# 1_ADC.net
KiCad netlist of a schematic drawn in Altium Designer
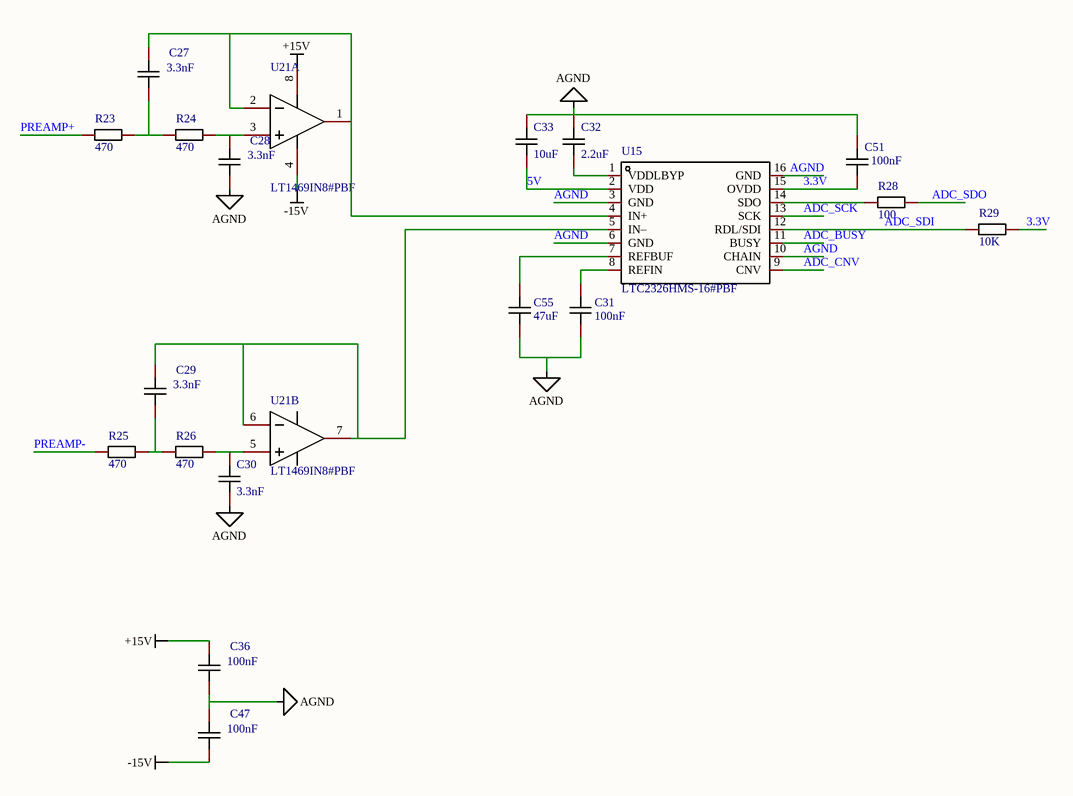
[diagram p0: 1_ADC.schdoc]

(export (version "E")
  (design (tool "Eeschema 10.0.6"))
  (components
    (comp (ref "C27")
      (value "3.3nF")
      (description "容值:100nF;精度:±10%;额定电压:25V;温度系数:X7R;")
      (fields
        (field (name "MANUFACTURER") "SAMSUNG(三星)")
        (field (name "MANUFACTURER PART") "CL10B104KA8NNNC")
      )
      (libsource (lib "altium-import") (part "root_1_CL10B104KA8NNNC_"))
    )
    (comp (ref "C28")
      (value "3.3nF")
      (description "容值:100nF;精度:±10%;额定电压:25V;温度系数:X7R;")
      (fields
        (field (name "MANUFACTURER") "SAMSUNG(三星)")
        (field (name "MANUFACTURER PART") "CL10B104KA8NNNC")
      )
      (libsource (lib "altium-import") (part "root_1_CL10B104KA8NNNC_"))
    )
    (comp (ref "C29")
      (value "3.3nF")
      (description "容值:100nF;精度:±10%;额定电压:25V;温度系数:X7R;")
      (fields
        (field (name "MANUFACTURER") "SAMSUNG(三星)")
        (field (name "MANUFACTURER PART") "CL10B104KA8NNNC")
      )
      (libsource (lib "altium-import") (part "root_1_CL10B104KA8NNNC_"))
    )
    (comp (ref "C30")
      (value "3.3nF")
      (description "容值:100nF;精度:±10%;额定电压:25V;温度系数:X7R;")
      (fields
        (field (name "MANUFACTURER") "SAMSUNG(三星)")
        (field (name "MANUFACTURER PART") "CL10B104KA8NNNC")
      )
      (libsource (lib "altium-import") (part "root_1_CL10B104KA8NNNC_"))
    )
    (comp (ref "C31")
      (value "100nF")
      (description "容值:100nF;精度:±10%;额定电压:25V;温度系数:X7R;")
      (fields
        (field (name "MANUFACTURER") "SAMSUNG(三星)")
        (field (name "MANUFACTURER PART") "CL10B104KA8NNNC")
      )
      (libsource (lib "altium-import") (part "root_1_CL10B104KA8NNNC_"))
    )
    (comp (ref "C32")
      (value "2.2uF")
      (description "容值:100nF;精度:±10%;额定电压:25V;温度系数:X7R;")
      (fields
        (field (name "MANUFACTURER") "SAMSUNG(三星)")
        (field (name "MANUFACTURER PART") "CL10B104KA8NNNC")
      )
      (libsource (lib "altium-import") (part "root_1_CL10B104KA8NNNC_"))
    )
    (comp (ref "C33")
      (value "10uF")
      (description "容值:100nF;精度:±10%;额定电压:25V;温度系数:X7R;")
      (fields
        (field (name "MANUFACTURER") "SAMSUNG(三星)")
        (field (name "MANUFACTURER PART") "CL10B104KA8NNNC")
      )
      (libsource (lib "altium-import") (part "root_1_CL10B104KA8NNNC_"))
    )
    (comp (ref "C36")
      (value "100nF")
      (description "容值:100nF;精度:±10%;额定电压:25V;温度系数:X7R;")
      (fields
        (field (name "MANUFACTURER") "SAMSUNG(三星)")
        (field (name "MANUFACTURER PART") "CL10B104KA8NNNC")
      )
      (libsource (lib "altium-import") (part "root_1_CL10B104KA8NNNC_"))
    )
    (comp (ref "C47")
      (value "100nF")
      (description "容值:100nF;精度:±10%;额定电压:25V;温度系数:X7R;")
      (fields
        (field (name "MANUFACTURER") "SAMSUNG(三星)")
        (field (name "MANUFACTURER PART") "CL10B104KA8NNNC")
      )
      (libsource (lib "altium-import") (part "root_1_CL10B104KA8NNNC_"))
    )
    (comp (ref "C51")
      (value "100nF")
      (description "容值:100nF;精度:±10%;额定电压:25V;温度系数:X7R;")
      (fields
        (field (name "MANUFACTURER") "SAMSUNG(三星)")
        (field (name "MANUFACTURER PART") "CL10B104KA8NNNC")
      )
      (libsource (lib "altium-import") (part "root_1_CL10B104KA8NNNC_"))
    )
    (comp (ref "C55")
      (value "47uF")
      (fields (field (name "NAME") "47uF"))
      (libsource (lib "altium-import") (part "root_1_CAP_1210_"))
    )
    (comp (ref "R23")
      (value "470")
      (description "电阻类型:厚膜电阻;阻值:10k;精度:±1%;功率:1/10W;温度系数:±100ppm/;最大工作电压:75V;工作温度范围:-55~+155;")
      (fields (field (name "MANUFACTURER") "UniOhm") (field (name "MANUFACTURER PART") "0603WAF4700T5E"))
      (libsource (lib "altium-import") (part "root_0_470_"))
    )
    (comp (ref "R24")
      (value "470")
      (description "电阻类型:厚膜电阻;阻值:10k;精度:±1%;功率:1/10W;温度系数:±100ppm/;最大工作电压:75V;工作温度范围:-55~+155;")
      (fields (field (name "MANUFACTURER") "UniOhm") (field (name "MANUFACTURER PART") "0603WAF4700T5E"))
      (libsource (lib "altium-import") (part "root_0_470_"))
    )
    (comp (ref "R25")
      (value "470")
      (description "电阻类型:厚膜电阻;阻值:10k;精度:±1%;功率:1/10W;温度系数:±100ppm/;最大工作电压:75V;工作温度范围:-55~+155;")
      (fields (field (name "MANUFACTURER") "UniOhm") (field (name "MANUFACTURER PART") "0603WAF4700T5E"))
      (libsource (lib "altium-import") (part "root_0_470_"))
    )
    (comp (ref "R26")
      (value "470")
      (description "电阻类型:厚膜电阻;阻值:10k;精度:±1%;功率:1/10W;温度系数:±100ppm/;最大工作电压:75V;工作温度范围:-55~+155;")
      (fields (field (name "MANUFACTURER") "UniOhm") (field (name "MANUFACTURER PART") "0603WAF4700T5E"))
      (libsource (lib "altium-import") (part "root_0_470_"))
    )
    (comp (ref "R28")
      (value "100")
      (fields (field (name "NAME") "100"))
      (libsource (lib "altium-import") (part "root_0_Res_0603_"))
    )
    (comp (ref "R29")
      (value "10K")
      (fields (field (name "NAME") "10K"))
      (libsource (lib "altium-import") (part "root_0_Res_0603_"))
    )
    (comp (ref "U15")
      (value "LTC2326HMS-16#PBF")
      (fields (field (name "NAME") "LTC2326HMS-16#PBF") (field (name "MANUFACTURER") "ADI(亚德诺)/LINEAR"))
      (libsource (lib "altium-import") (part "root_0_LTC2326HMS-16#PBF_"))
    )
    (comp (ref "U21")
      (value "LT1469IN8#PBF")
      (fields (field (name "NAME") "LT1469IN8#PBF") (field (name "MANUFACTURER") "ADI(亚德诺)/LINEAR"))
      (libsource (lib "altium-import") (part "root_0_LT1469IN8#PBF_"))
    )
  )
  (nets
    (net (code "1") (name "+15V") (class "Default")
      (node (ref "C36") (pin "2") (pinfunction "2_2") (pintype "passive"))
      (node (ref "U21") (pin "8") (pinfunction "V+_8") (pintype "passive"))
    )
    (net (code "2") (name "-15V") (class "Default")
      (node (ref "C47") (pin "1") (pinfunction "1_1") (pintype "passive"))
      (node (ref "U21") (pin "4") (pinfunction "V-_4") (pintype "passive"))
    )
    (net (code "3") (name "/3.3V") (class "Default")
      (node (ref "C51") (pin "1") (pinfunction "1_1") (pintype "passive"))
      (node (ref "R29") (pin "2") (pinfunction "2_2") (pintype "passive"))
      (node (ref "U15") (pin "15") (pinfunction "OVDD_15") (pintype "passive"))
    )
    (net (code "4") (name "/5V") (class "Default")
      (node (ref "C33") (pin "1") (pinfunction "1_1") (pintype "passive"))
      (node (ref "U15") (pin "2") (pinfunction "VDD_2") (pintype "passive"))
    )
    (net (code "5") (name "/ADC_BUSY") (class "Default")
      (node (ref "U15") (pin "11") (pinfunction "BUSY_11") (pintype "passive"))
    )
    (net (code "6") (name "/ADC_CNV") (class "Default")
      (node (ref "U15") (pin "9") (pinfunction "CNV_9") (pintype "passive"))
    )
    (net (code "7") (name "/ADC_SCK") (class "Default")
      (node (ref "U15") (pin "13") (pinfunction "SCK_13") (pintype "passive"))
    )
    (net (code "8") (name "/ADC_SDI") (class "Default")
      (node (ref "R29") (pin "1") (pinfunction "1_1") (pintype "passive"))
      (node (ref "U15") (pin "12") (pinfunction "RDL/SDI_12") (pintype "passive"))
    )
    (net (code "9") (name "/ADC_SDO") (class "Default")
      (node (ref "R28") (pin "2") (pinfunction "2_2") (pintype "passive"))
    )
    (net (code "10") (name "/PREAMP+") (class "Default")
      (node (ref "R23") (pin "1") (pinfunction "1_1") (pintype "passive"))
    )
    (net (code "11") (name "/PREAMP-") (class "Default")
      (node (ref "R25") (pin "1") (pinfunction "1_1") (pintype "passive"))
    )
    (net (code "12") (name "AGND") (class "Default")
      (node (ref "C28") (pin "1") (pinfunction "1_1") (pintype "passive"))
      (node (ref "C30") (pin "1") (pinfunction "1_1") (pintype "passive"))
      (node (ref "C31") (pin "1") (pinfunction "1_1") (pintype "passive"))
      (node (ref "C32") (pin "2") (pinfunction "2_2") (pintype "passive"))
      (node (ref "C33") (pin "2") (pinfunction "2_2") (pintype "passive"))
      (node (ref "C36") (pin "1") (pinfunction "1_1") (pintype "passive"))
      (node (ref "C47") (pin "2") (pinfunction "2_2") (pintype "passive"))
      (node (ref "C51") (pin "2") (pinfunction "2_2") (pintype "passive"))
      (node (ref "C55") (pin "2") (pinfunction "2_2") (pintype "passive"))
      (node (ref "U15") (pin "10") (pinfunction "CHAIN_10") (pintype "passive"))
      (node (ref "U15") (pin "16") (pinfunction "GND_16") (pintype "passive"))
      (node (ref "U15") (pin "3") (pinfunction "GND_3") (pintype "passive"))
      (node (ref "U15") (pin "6") (pinfunction "GND_6") (pintype "passive"))
    )
    (net (code "13") (name "Net-(C27-Pad1)") (class "Default")
      (node (ref "C27") (pin "1") (pinfunction "1_1") (pintype "passive"))
      (node (ref "R23") (pin "2") (pinfunction "2_2") (pintype "passive"))
      (node (ref "R24") (pin "1") (pinfunction "1_1") (pintype "passive"))
    )
    (net (code "14") (name "Net-(C29-Pad1)") (class "Default")
      (node (ref "C29") (pin "1") (pinfunction "1_1") (pintype "passive"))
      (node (ref "R25") (pin "2") (pinfunction "2_2") (pintype "passive"))
      (node (ref "R26") (pin "1") (pinfunction "1_1") (pintype "passive"))
    )
    (net (code "15") (name "Net-(U15-IN+)") (class "Default")
      (node (ref "C27") (pin "2") (pinfunction "2_2") (pintype "passive"))
      (node (ref "U15") (pin "4") (pinfunction "IN+_4") (pintype "passive"))
      (node (ref "U21") (pin "1") (pinfunction "OUT_A_1") (pintype "passive"))
      (node (ref "U21") (pin "2") (pinfunction "-IN_A_2") (pintype "passive"))
    )
    (net (code "16") (name "Net-(U15-IN–)") (class "Default")
      (node (ref "C29") (pin "2") (pinfunction "2_2") (pintype "passive"))
      (node (ref "U15") (pin "5") (pinfunction "IN–_5") (pintype "passive"))
      (node (ref "U21") (pin "6") (pinfunction "-IN_B_6") (pintype "passive"))
      (node (ref "U21") (pin "7") (pinfunction "OUT_B_7") (pintype "passive"))
    )
    (net (code "17") (name "Net-(U15-REFBUF)") (class "Default")
      (node (ref "C55") (pin "1") (pinfunction "1_1") (pintype "passive"))
      (node (ref "U15") (pin "7") (pinfunction "REFBUF_7") (pintype "passive"))
    )
    (net (code "18") (name "Net-(U15-REFIN)") (class "Default")
      (node (ref "C31") (pin "2") (pinfunction "2_2") (pintype "passive"))
      (node (ref "U15") (pin "8") (pinfunction "REFIN_8") (pintype "passive"))
    )
    (net (code "19") (name "Net-(U15-SDO)") (class "Default")
      (node (ref "R28") (pin "1") (pinfunction "1_1") (pintype "passive"))
      (node (ref "U15") (pin "14") (pinfunction "SDO_14") (pintype "passive"))
    )
    (net (code "20") (name "Net-(U15-VDDLBYP)") (class "Default")
      (node (ref "C32") (pin "1") (pinfunction "1_1") (pintype "passive"))
      (node (ref "U15") (pin "1") (pinfunction "VDDLBYP_1") (pintype "passive"))
    )
    (net (code "21") (name "Net-(U21A-+IN_A)") (class "Default")
      (node (ref "C28") (pin "2") (pinfunction "2_2") (pintype "passive"))
      (node (ref "R24") (pin "2") (pinfunction "2_2") (pintype "passive"))
      (node (ref "U21") (pin "3") (pinfunction "+IN_A_3") (pintype "passive"))
    )
    (net (code "22") (name "Net-(U21B-+IN_B)") (class "Default")
      (node (ref "C30") (pin "2") (pinfunction "2_2") (pintype "passive"))
      (node (ref "R26") (pin "2") (pinfunction "2_2") (pintype "passive"))
      (node (ref "U21") (pin "5") (pinfunction "+IN_B_5") (pintype "passive"))
    )
  )
)
